# ldet_loop_preamp.net
KiCad netlist of a schematic drawn in EAGLE
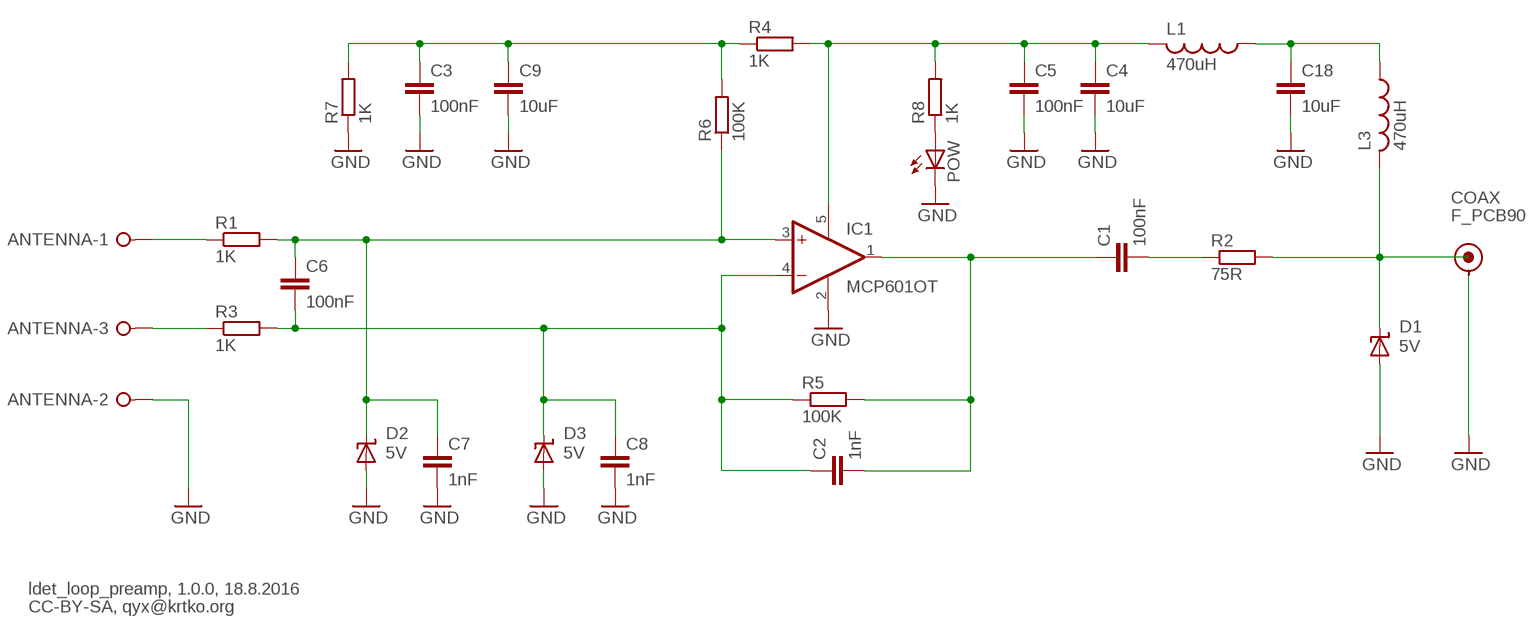
[diagram p0: schematic, sheet 1]

(export (version "E")
  (design (tool "Eeschema 10.0.6"))
  (components
    (comp (ref "ANTENNA")
      (value "W237-3E")
      (footprint "eagle-import:W237-3E")
      (libsource (lib "eagle-import") (part "W237-3E"))
    )
    (comp (ref "C1")
      (value "100nF")
      (footprint "eagle-import:C0603")
      (libsource (lib "eagle-import") (part "C-EUC0603"))
    )
    (comp (ref "C2")
      (value "1nF")
      (footprint "eagle-import:C0603")
      (libsource (lib "eagle-import") (part "C-EUC0603"))
    )
    (comp (ref "C3")
      (value "100nF")
      (footprint "eagle-import:C0603")
      (libsource (lib "eagle-import") (part "C-EUC0603"))
    )
    (comp (ref "C4")
      (value "10uF")
      (footprint "eagle-import:C1206")
      (libsource (lib "eagle-import") (part "C-EUC1206"))
    )
    (comp (ref "C5")
      (value "100nF")
      (footprint "eagle-import:C0603")
      (libsource (lib "eagle-import") (part "C-EUC0603"))
    )
    (comp (ref "C6")
      (value "100nF")
      (footprint "eagle-import:C0603")
      (libsource (lib "eagle-import") (part "C-EUC0603"))
    )
    (comp (ref "C7")
      (value "1nF")
      (footprint "eagle-import:C0603")
      (libsource (lib "eagle-import") (part "C-EUC0603"))
    )
    (comp (ref "C8")
      (value "1nF")
      (footprint "eagle-import:C0603")
      (libsource (lib "eagle-import") (part "C-EUC0603"))
    )
    (comp (ref "C9")
      (value "10uF")
      (footprint "eagle-import:C1206")
      (libsource (lib "eagle-import") (part "C-EUC1206"))
    )
    (comp (ref "C18")
      (value "10uF")
      (footprint "eagle-import:C1206")
      (libsource (lib "eagle-import") (part "C-EUC1206"))
    )
    (comp (ref "COAX")
      (value "F_PCB90")
      (footprint "eagle-import:F_PCB_90")
      (libsource (lib "eagle-import") (part "F_PCB90"))
    )
    (comp (ref "D1")
      (value "5V")
      (footprint "eagle-import:SMBJ")
      (libsource (lib "eagle-import") (part "SUPPRESSOR-SMBJ"))
    )
    (comp (ref "D2")
      (value "5V")
      (footprint "eagle-import:SMBJ")
      (libsource (lib "eagle-import") (part "SUPPRESSOR-SMBJ"))
    )
    (comp (ref "D3")
      (value "5V")
      (footprint "eagle-import:SMBJ")
      (libsource (lib "eagle-import") (part "SUPPRESSOR-SMBJ"))
    )
    (comp (ref "IC1")
      (value "MCP601OT")
      (footprint "eagle-import:SOT23-5")
      (libsource (lib "eagle-import") (part "MCP601OT"))
    )
    (comp (ref "L1")
      (value "470uH")
      (footprint "eagle-import:L3225M")
      (fields (field (name "MPN") "LQH32CN471K23L"))
      (libsource (lib "eagle-import") (part "L-USL3225M"))
    )
    (comp (ref "L3")
      (value "470uH")
      (footprint "eagle-import:L3225M")
      (fields (field (name "MPN") "LQH32CN471K23L"))
      (libsource (lib "eagle-import") (part "L-USL3225M"))
    )
    (comp (ref "POW")
      (value "LEDCHIPLED_0603")
      (footprint "eagle-import:CHIPLED_0603")
      (libsource (lib "eagle-import") (part "LEDCHIPLED_0603"))
    )
    (comp (ref "R1")
      (value "1K")
      (footprint "eagle-import:R0603")
      (libsource (lib "eagle-import") (part "R-EU_R0603"))
    )
    (comp (ref "R2")
      (value "75R")
      (footprint "eagle-import:R0603")
      (libsource (lib "eagle-import") (part "R-EU_R0603"))
    )
    (comp (ref "R3")
      (value "1K")
      (footprint "eagle-import:R0603")
      (libsource (lib "eagle-import") (part "R-EU_R0603"))
    )
    (comp (ref "R4")
      (value "1K")
      (footprint "eagle-import:R0603")
      (libsource (lib "eagle-import") (part "R-EU_R0603"))
    )
    (comp (ref "R5")
      (value "100K")
      (footprint "eagle-import:R0603")
      (libsource (lib "eagle-import") (part "R-EU_R0603"))
    )
    (comp (ref "R6")
      (value "100K")
      (footprint "eagle-import:R0603")
      (libsource (lib "eagle-import") (part "R-EU_R0603"))
    )
    (comp (ref "R7")
      (value "1K")
      (footprint "eagle-import:R0603")
      (libsource (lib "eagle-import") (part "R-EU_R0603"))
    )
    (comp (ref "R8")
      (value "1K")
      (footprint "eagle-import:R0603")
      (libsource (lib "eagle-import") (part "R-EU_R0603"))
    )
  )
  (nets
    (net (code "1") (name "GND") (class "Default")
      (node (ref "ANTENNA") (pin "2") (pinfunction "KL_2") (pintype "passive"))
      (node (ref "C18") (pin "2") (pinfunction "2_2") (pintype "passive"))
      (node (ref "C3") (pin "2") (pinfunction "2_2") (pintype "passive"))
      (node (ref "C4") (pin "2") (pinfunction "2_2") (pintype "passive"))
      (node (ref "C5") (pin "2") (pinfunction "2_2") (pintype "passive"))
      (node (ref "C7") (pin "2") (pinfunction "2_2") (pintype "passive"))
      (node (ref "C8") (pin "2") (pinfunction "2_2") (pintype "passive"))
      (node (ref "C9") (pin "2") (pinfunction "2_2") (pintype "passive"))
      (node (ref "COAX") (pin "S1") (pinfunction "SHIELD_S1") (pintype "bidirectional"))
      (node (ref "COAX") (pin "S2") (pinfunction "SHIELD_S2") (pintype "bidirectional"))
      (node (ref "COAX") (pin "S3") (pinfunction "SHIELD_S3") (pintype "bidirectional"))
      (node (ref "COAX") (pin "S4") (pinfunction "SHIELD_S4") (pintype "bidirectional"))
      (node (ref "D1") (pin "A") (pinfunction "A_A") (pintype "passive"))
      (node (ref "D2") (pin "A") (pinfunction "A_A") (pintype "passive"))
      (node (ref "D3") (pin "A") (pinfunction "A_A") (pintype "passive"))
      (node (ref "IC1") (pin "2") (pinfunction "V-_2") (pintype "power_in"))
      (node (ref "POW") (pin "C") (pinfunction "C_C") (pintype "passive"))
      (node (ref "R7") (pin "1") (pinfunction "1_1") (pintype "passive"))
    )
    (net (code "2") (name "Net-(ANTENNAA-KL)") (class "Default")
      (node (ref "ANTENNA") (pin "1") (pinfunction "KL_1") (pintype "passive"))
      (node (ref "R1") (pin "1") (pinfunction "1_1") (pintype "passive"))
    )
    (net (code "3") (name "Net-(ANTENNAC-KL)") (class "Default")
      (node (ref "ANTENNA") (pin "3") (pinfunction "KL_3") (pintype "passive"))
      (node (ref "R3") (pin "1") (pinfunction "1_1") (pintype "passive"))
    )
    (net (code "4") (name "Net-(C1-Pad2)") (class "Default")
      (node (ref "C1") (pin "2") (pinfunction "2_2") (pintype "passive"))
      (node (ref "R2") (pin "1") (pinfunction "1_1") (pintype "passive"))
    )
    (net (code "5") (name "Net-(C3-Pad1)") (class "Default")
      (node (ref "C3") (pin "1") (pinfunction "1_1") (pintype "passive"))
      (node (ref "C9") (pin "1") (pinfunction "1_1") (pintype "passive"))
      (node (ref "R4") (pin "1") (pinfunction "1_1") (pintype "passive"))
      (node (ref "R6") (pin "2") (pinfunction "2_2") (pintype "passive"))
      (node (ref "R7") (pin "2") (pinfunction "2_2") (pintype "passive"))
    )
    (net (code "6") (name "Net-(C18-Pad1)") (class "Default")
      (node (ref "C18") (pin "1") (pinfunction "1_1") (pintype "passive"))
      (node (ref "L1") (pin "1") (pinfunction "1_1") (pintype "passive"))
      (node (ref "L3") (pin "1") (pinfunction "1_1") (pintype "passive"))
    )
    (net (code "7") (name "Net-(COAX-CENTER)") (class "Default")
      (node (ref "COAX") (pin "C") (pinfunction "CENTER_C") (pintype "bidirectional"))
      (node (ref "D1") (pin "C") (pinfunction "C_C") (pintype "passive"))
      (node (ref "L3") (pin "2") (pinfunction "2_2") (pintype "passive"))
      (node (ref "R2") (pin "2") (pinfunction "2_2") (pintype "passive"))
    )
    (net (code "8") (name "Net-(IC1-+IN)") (class "Default")
      (node (ref "C6") (pin "1") (pinfunction "1_1") (pintype "passive"))
      (node (ref "C7") (pin "1") (pinfunction "1_1") (pintype "passive"))
      (node (ref "D2") (pin "C") (pinfunction "C_C") (pintype "passive"))
      (node (ref "IC1") (pin "3") (pinfunction "+IN_3") (pintype "input"))
      (node (ref "R1") (pin "2") (pinfunction "2_2") (pintype "passive"))
      (node (ref "R6") (pin "1") (pinfunction "1_1") (pintype "passive"))
    )
    (net (code "9") (name "Net-(IC1--IN)") (class "Default")
      (node (ref "C2") (pin "1") (pinfunction "1_1") (pintype "passive"))
      (node (ref "C6") (pin "2") (pinfunction "2_2") (pintype "passive"))
      (node (ref "C8") (pin "1") (pinfunction "1_1") (pintype "passive"))
      (node (ref "D3") (pin "C") (pinfunction "C_C") (pintype "passive"))
      (node (ref "IC1") (pin "4") (pinfunction "-IN_4") (pintype "input"))
      (node (ref "R3") (pin "2") (pinfunction "2_2") (pintype "passive"))
      (node (ref "R5") (pin "1") (pinfunction "1_1") (pintype "passive"))
    )
    (net (code "10") (name "Net-(IC1-OUT)") (class "Default")
      (node (ref "C1") (pin "1") (pinfunction "1_1") (pintype "passive"))
      (node (ref "C2") (pin "2") (pinfunction "2_2") (pintype "passive"))
      (node (ref "IC1") (pin "1") (pinfunction "OUT_1") (pintype "output"))
      (node (ref "R5") (pin "2") (pinfunction "2_2") (pintype "passive"))
    )
    (net (code "11") (name "Net-(IC1-V+)") (class "Default")
      (node (ref "C4") (pin "1") (pinfunction "1_1") (pintype "passive"))
      (node (ref "C5") (pin "1") (pinfunction "1_1") (pintype "passive"))
      (node (ref "IC1") (pin "5") (pinfunction "V+_5") (pintype "power_in"))
      (node (ref "L1") (pin "2") (pinfunction "2_2") (pintype "passive"))
      (node (ref "R4") (pin "2") (pinfunction "2_2") (pintype "passive"))
      (node (ref "R8") (pin "2") (pinfunction "2_2") (pintype "passive"))
    )
    (net (code "12") (name "Net-(POW-PadA)") (class "Default")
      (node (ref "POW") (pin "A") (pinfunction "A_A") (pintype "passive"))
      (node (ref "R8") (pin "1") (pinfunction "1_1") (pintype "passive"))
    )
  )
)
